# breadboard-E03.net
KiCad netlist of a schematic drawn in EAGLE
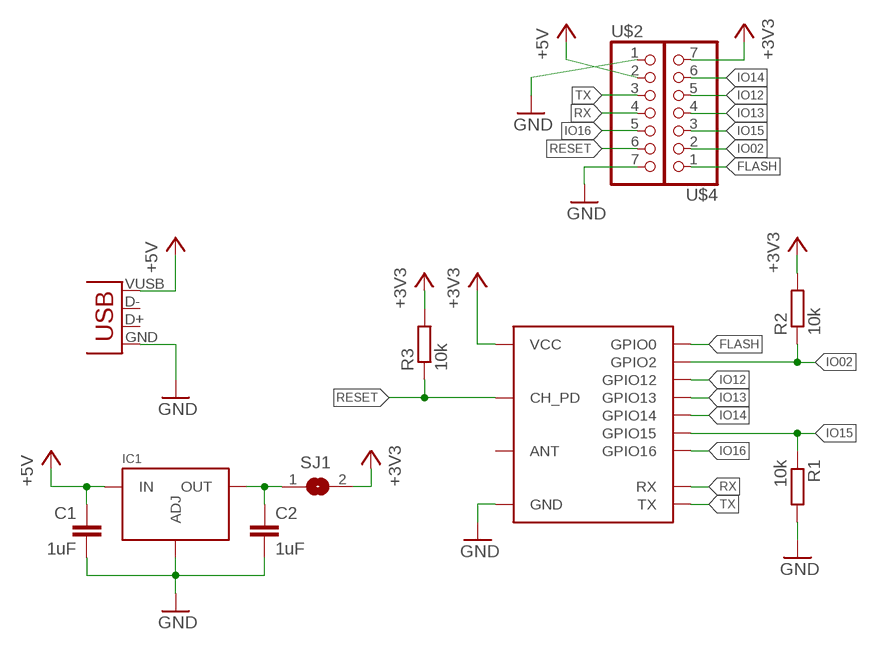
[diagram p0: schematic, sheet 1]

(export (version "E")
  (design (tool "Eeschema 10.0.6"))
  (components
    (comp (ref "C1")
      (value "1uF")
      (footprint "eagle-import:C0805")
      (libsource (lib "eagle-import") (part "C-EUC0805"))
    )
    (comp (ref "C2")
      (value "1uF")
      (footprint "eagle-import:C0805")
      (libsource (lib "eagle-import") (part "C-EUC0805"))
    )
    (comp (ref "CON1")
      (value "USBMICRO-NO_CENTER")
      (footprint "eagle-import:USB-MICRO-SMD-NO_CENTER")
      (libsource (lib "eagle-import") (part "USBMICRO-NO_CENTER"))
    )
    (comp (ref "IC1")
      (value "REGULATOR-TLV1117SOT223")
      (footprint "eagle-import:SOT223")
      (libsource (lib "eagle-import") (part "REGULATOR-TLV1117SOT223"))
    )
    (comp (ref "R1")
      (value "10k")
      (footprint "eagle-import:R0603")
      (libsource (lib "eagle-import") (part "R-EU_R0603"))
    )
    (comp (ref "R2")
      (value "10k")
      (footprint "eagle-import:R0603")
      (libsource (lib "eagle-import") (part "R-EU_R0603"))
    )
    (comp (ref "R3")
      (value "10k")
      (footprint "eagle-import:R0603")
      (libsource (lib "eagle-import") (part "R-EU_R0603"))
    )
    (comp (ref "SJ1") (value "SJ") (footprint "eagle-import:SJ") (libsource (lib "eagle-import") (part "SJ")))
    (comp (ref "U$1")
      (value "ESP8266-03")
      (footprint "eagle-import:ESP8266-ESP-03")
      (libsource (lib "eagle-import") (part "ESP8266-03"))
    )
    (comp (ref "U$2")
      (value "GENERIC-1X7")
      (footprint "eagle-import:PINHEADER-100MIL-1X7")
      (libsource (lib "eagle-import") (part "GENERIC-1X7"))
    )
    (comp (ref "U$4")
      (value "GENERIC-1X7")
      (footprint "eagle-import:PINHEADER-100MIL-1X7")
      (libsource (lib "eagle-import") (part "GENERIC-1X7"))
    )
  )
  (nets
    (net (code "1") (name "+3V3") (class "Default")
      (node (ref "R2") (pin "2") (pinfunction "2_2") (pintype "passive"))
      (node (ref "R3") (pin "2") (pinfunction "2_2") (pintype "passive"))
      (node (ref "SJ1") (pin "2") (pinfunction "2_2") (pintype "passive"))
      (node (ref "U$1") (pin "P$8") (pinfunction "VCC_P$8") (pintype "bidirectional"))
      (node (ref "U$4") (pin "7") (pinfunction "7_7") (pintype "passive"))
    )
    (net (code "2") (name "+5V") (class "Default")
      (node (ref "C1") (pin "1") (pinfunction "1_1") (pintype "passive"))
      (node (ref "CON1") (pin "VUSB") (pinfunction "VBUS_VUSB") (pintype "bidirectional"))
      (node (ref "IC1") (pin "3") (pinfunction "IN_3") (pintype "bidirectional"))
      (node (ref "U$2") (pin "2") (pinfunction "2_2") (pintype "passive"))
    )
    (net (code "3") (name "FLASH") (class "Default")
      (node (ref "U$1") (pin "P$14") (pinfunction "GPIO0_P$14") (pintype "bidirectional"))
      (node (ref "U$4") (pin "1") (pinfunction "1_1") (pintype "passive"))
    )
    (net (code "4") (name "GND") (class "Default")
      (node (ref "C1") (pin "2") (pinfunction "2_2") (pintype "passive"))
      (node (ref "C2") (pin "2") (pinfunction "2_2") (pintype "passive"))
      (node (ref "CON1") (pin "GND") (pinfunction "GND_GND") (pintype "bidirectional"))
      (node (ref "IC1") (pin "1") (pinfunction "ADJ_1") (pintype "bidirectional"))
      (node (ref "R1") (pin "2") (pinfunction "2_2") (pintype "passive"))
      (node (ref "U$1") (pin "P$1") (pinfunction "GND_P$1") (pintype "bidirectional"))
      (node (ref "U$2") (pin "1") (pinfunction "1_1") (pintype "passive"))
      (node (ref "U$2") (pin "7") (pinfunction "7_7") (pintype "passive"))
    )
    (net (code "5") (name "IO02") (class "Default")
      (node (ref "R2") (pin "1") (pinfunction "1_1") (pintype "passive"))
      (node (ref "U$1") (pin "P$13") (pinfunction "GPIO2_P$13") (pintype "bidirectional"))
      (node (ref "U$4") (pin "2") (pinfunction "2_2") (pintype "passive"))
    )
    (net (code "6") (name "IO12") (class "Default")
      (node (ref "U$1") (pin "P$10") (pinfunction "GPIO12_P$10") (pintype "bidirectional"))
      (node (ref "U$4") (pin "5") (pinfunction "5_5") (pintype "passive"))
    )
    (net (code "7") (name "IO13") (class "Default")
      (node (ref "U$1") (pin "P$11") (pinfunction "GPIO13_P$11") (pintype "bidirectional"))
      (node (ref "U$4") (pin "4") (pinfunction "4_4") (pintype "passive"))
    )
    (net (code "8") (name "IO14") (class "Default")
      (node (ref "U$1") (pin "P$9") (pinfunction "GPIO14_P$9") (pintype "bidirectional"))
      (node (ref "U$4") (pin "6") (pinfunction "6_6") (pintype "passive"))
    )
    (net (code "9") (name "IO15") (class "Default")
      (node (ref "R1") (pin "1") (pinfunction "1_1") (pintype "passive"))
      (node (ref "U$1") (pin "P$12") (pinfunction "GPIO15_P$12") (pintype "bidirectional"))
      (node (ref "U$4") (pin "3") (pinfunction "3_3") (pintype "passive"))
    )
    (net (code "10") (name "IO16") (class "Default")
      (node (ref "U$1") (pin "P$5") (pinfunction "GPIO16_P$5") (pintype "bidirectional"))
      (node (ref "U$2") (pin "5") (pinfunction "5_5") (pintype "passive"))
    )
    (net (code "11") (name "Net-(C2-Pad1)") (class "Default")
      (node (ref "C2") (pin "1") (pinfunction "1_1") (pintype "passive"))
      (node (ref "IC1") (pin "2") (pinfunction "OUT_2") (pintype "bidirectional"))
      (node (ref "IC1") (pin "4") (pinfunction "OUT_4") (pintype "bidirectional"))
      (node (ref "SJ1") (pin "1") (pinfunction "1_1") (pintype "passive"))
    )
    (net (code "12") (name "RESET") (class "Default")
      (node (ref "R3") (pin "1") (pinfunction "1_1") (pintype "passive"))
      (node (ref "U$1") (pin "P$6") (pinfunction "CH_PD_P$6") (pintype "bidirectional"))
      (node (ref "U$2") (pin "6") (pinfunction "6_6") (pintype "passive"))
    )
    (net (code "13") (name "RX") (class "Default")
      (node (ref "U$1") (pin "P$4") (pinfunction "RX_P$4") (pintype "bidirectional"))
      (node (ref "U$2") (pin "4") (pinfunction "4_4") (pintype "passive"))
    )
    (net (code "14") (name "TX") (class "Default")
      (node (ref "U$1") (pin "P$3") (pinfunction "TX_P$3") (pintype "bidirectional"))
      (node (ref "U$2") (pin "3") (pinfunction "3_3") (pintype "passive"))
    )
    (net (code "15") (name "unconnected-(CON1-PadD+)") (class "Default")
      (node (ref "CON1") (pin "D+") (pinfunction "D+_D+") (pintype "bidirectional"))
    )
    (net (code "16") (name "unconnected-(CON1-PadD-)") (class "Default")
      (node (ref "CON1") (pin "D-") (pinfunction "D-_D-") (pintype "bidirectional"))
    )
    (net (code "17") (name "unconnected-(U$1-ANT-PadP$7)") (class "Default")
      (node (ref "U$1") (pin "P$7") (pinfunction "ANT_P$7") (pintype "bidirectional"))
    )
  )
)
